# czujnik_smrodu_mkrwan_v02.net
KiCad netlist of a schematic drawn in EAGLE
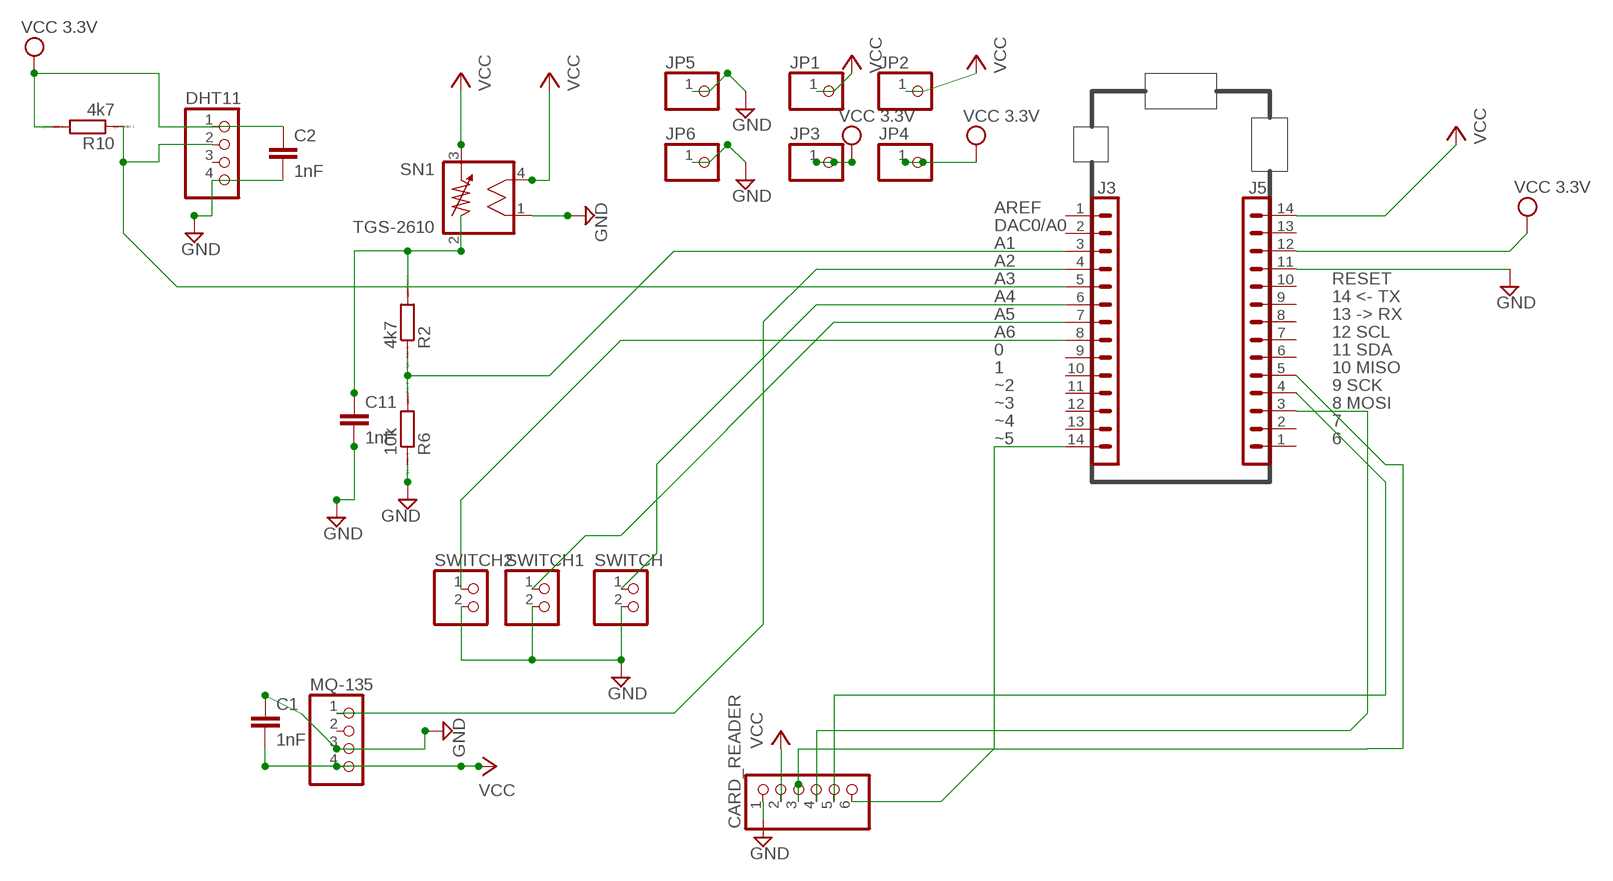
[diagram p0: schematic, sheet 1]

(export (version "E")
  (design (tool "Eeschema 10.0.6"))
  (components
    (comp (ref "C1")
      (value "1nF")
      (footprint "eagle-import:C2.5-3")
      (libsource (lib "eagle-import") (part "C2,5-3"))
    )
    (comp (ref "C2")
      (value "1nF")
      (footprint "eagle-import:C2.5-3")
      (libsource (lib "eagle-import") (part "C2,5-3"))
    )
    (comp (ref "C11")
      (value "1nF")
      (footprint "eagle-import:C2.5-3")
      (libsource (lib "eagle-import") (part "C2,5-3"))
    )
    (comp (ref "CARD_READER")
      (value "PINHD-1X6")
      (footprint "eagle-import:1X06")
      (libsource (lib "eagle-import") (part "PINHD-1X6"))
    )
    (comp (ref "DHT11")
      (value "PINHD-1X4")
      (footprint "eagle-import:1X04")
      (libsource (lib "eagle-import") (part "PINHD-1X4"))
    )
    (comp (ref "J3")
      (value "DNP")
      (footprint "eagle-import:1X14_SMD_TH")
      (fields (field (name "MANUFACTURER") "ELDECO"))
      (libsource (lib "eagle-import") (part "PINHD-1X14-SMTH-SMD"))
    )
    (comp (ref "J5")
      (value "DNP")
      (footprint "eagle-import:1X14_SMD_TH")
      (fields (field (name "MANUFACTURER") "ELDECO"))
      (libsource (lib "eagle-import") (part "PINHD-1X14-SMTH-SMD"))
    )
    (comp (ref "JP1")
      (value "PINHD-1X1")
      (footprint "eagle-import:1X01")
      (libsource (lib "eagle-import") (part "PINHD-1X1"))
    )
    (comp (ref "JP2")
      (value "PINHD-1X1")
      (footprint "eagle-import:1X01")
      (libsource (lib "eagle-import") (part "PINHD-1X1"))
    )
    (comp (ref "JP3")
      (value "PINHD-1X1")
      (footprint "eagle-import:1X01")
      (libsource (lib "eagle-import") (part "PINHD-1X1"))
    )
    (comp (ref "JP4")
      (value "PINHD-1X1")
      (footprint "eagle-import:1X01")
      (libsource (lib "eagle-import") (part "PINHD-1X1"))
    )
    (comp (ref "JP5")
      (value "PINHD-1X1")
      (footprint "eagle-import:1X01")
      (libsource (lib "eagle-import") (part "PINHD-1X1"))
    )
    (comp (ref "JP6")
      (value "PINHD-1X1")
      (footprint "eagle-import:1X01")
      (libsource (lib "eagle-import") (part "PINHD-1X1"))
    )
    (comp (ref "MQ-135")
      (value "PINHD-1X4")
      (footprint "eagle-import:1X04")
      (libsource (lib "eagle-import") (part "PINHD-1X4"))
    )
    (comp (ref "R2")
      (value "4k7")
      (footprint "eagle-import:0207_10")
      (libsource (lib "eagle-import") (part "R0207/10"))
    )
    (comp (ref "R6")
      (value "10k")
      (footprint "eagle-import:0207_10")
      (libsource (lib "eagle-import") (part "R0207/10"))
    )
    (comp (ref "R10")
      (value "4k7")
      (footprint "eagle-import:0207_10")
      (libsource (lib "eagle-import") (part "R0207/10"))
    )
    (comp (ref "SN1")
      (value "TGS-2610")
      (footprint "eagle-import:TGS-2610")
      (libsource (lib "eagle-import") (part "TGS-2610"))
    )
    (comp (ref "SWITCH")
      (value "PINHD-1X2")
      (footprint "eagle-import:1X02")
      (libsource (lib "eagle-import") (part "PINHD-1X2"))
    )
    (comp (ref "SWITCH1")
      (value "PINHD-1X2")
      (footprint "eagle-import:1X02")
      (libsource (lib "eagle-import") (part "PINHD-1X2"))
    )
    (comp (ref "SWITCH2")
      (value "PINHD-1X2")
      (footprint "eagle-import:1X02")
      (libsource (lib "eagle-import") (part "PINHD-1X2"))
    )
  )
  (nets
    (net (code "1") (name "GND") (class "Default")
      (node (ref "C1") (pin "1") (pinfunction "1_1") (pintype "passive"))
      (node (ref "C11") (pin "2") (pinfunction "2_2") (pintype "passive"))
      (node (ref "C2") (pin "2") (pinfunction "2_2") (pintype "passive"))
      (node (ref "CARD_READER") (pin "1") (pinfunction "1_1") (pintype "passive"))
      (node (ref "DHT11") (pin "4") (pinfunction "4_4") (pintype "passive"))
      (node (ref "J5") (pin "11") (pinfunction "11_11") (pintype "passive"))
      (node (ref "JP5") (pin "1") (pinfunction "1_1") (pintype "passive"))
      (node (ref "JP6") (pin "1") (pinfunction "1_1") (pintype "passive"))
      (node (ref "MQ-135") (pin "3") (pinfunction "3_3") (pintype "passive"))
      (node (ref "R6") (pin "1") (pinfunction "1_1") (pintype "passive"))
      (node (ref "SN1") (pin "1") (pinfunction "1_1") (pintype "passive"))
      (node (ref "SWITCH") (pin "2") (pinfunction "2_2") (pintype "passive"))
      (node (ref "SWITCH1") (pin "2") (pinfunction "2_2") (pintype "passive"))
      (node (ref "SWITCH2") (pin "2") (pinfunction "2_2") (pintype "passive"))
    )
    (net (code "2") (name "Net-(C11-Pad1)") (class "Default")
      (node (ref "C11") (pin "1") (pinfunction "1_1") (pintype "passive"))
      (node (ref "R2") (pin "2") (pinfunction "2_2") (pintype "passive"))
      (node (ref "SN1") (pin "2") (pinfunction "2_2") (pintype "passive"))
    )
    (net (code "3") (name "Net-(CARD_READER-Pad3)") (class "Default")
      (node (ref "CARD_READER") (pin "3") (pinfunction "3_3") (pintype "passive"))
      (node (ref "J5") (pin "5") (pinfunction "5_5") (pintype "passive"))
    )
    (net (code "4") (name "Net-(CARD_READER-Pad4)") (class "Default")
      (node (ref "CARD_READER") (pin "4") (pinfunction "4_4") (pintype "passive"))
      (node (ref "J5") (pin "3") (pinfunction "3_3") (pintype "passive"))
    )
    (net (code "5") (name "Net-(CARD_READER-Pad5)") (class "Default")
      (node (ref "CARD_READER") (pin "5") (pinfunction "5_5") (pintype "passive"))
      (node (ref "J5") (pin "4") (pinfunction "4_4") (pintype "passive"))
    )
    (net (code "6") (name "Net-(CARD_READER-Pad6)") (class "Default")
      (node (ref "CARD_READER") (pin "6") (pinfunction "6_6") (pintype "passive"))
      (node (ref "J3") (pin "14") (pinfunction "14_14") (pintype "passive"))
    )
    (net (code "7") (name "Net-(DHT11-Pad2)") (class "Default")
      (node (ref "DHT11") (pin "2") (pinfunction "2_2") (pintype "passive"))
      (node (ref "J3") (pin "5") (pinfunction "5_5") (pintype "passive"))
      (node (ref "R10") (pin "1") (pinfunction "1_1") (pintype "passive"))
    )
    (net (code "8") (name "Net-(J3-Pad3)") (class "Default")
      (node (ref "J3") (pin "3") (pinfunction "3_3") (pintype "passive"))
      (node (ref "R2") (pin "1") (pinfunction "1_1") (pintype "passive"))
      (node (ref "R6") (pin "2") (pinfunction "2_2") (pintype "passive"))
    )
    (net (code "9") (name "Net-(J3-Pad4)") (class "Default")
      (node (ref "J3") (pin "4") (pinfunction "4_4") (pintype "passive"))
      (node (ref "MQ-135") (pin "1") (pinfunction "1_1") (pintype "passive"))
    )
    (net (code "10") (name "Net-(J3-Pad6)") (class "Default")
      (node (ref "J3") (pin "6") (pinfunction "6_6") (pintype "passive"))
      (node (ref "SWITCH") (pin "1") (pinfunction "1_1") (pintype "passive"))
    )
    (net (code "11") (name "Net-(J3-Pad7)") (class "Default")
      (node (ref "J3") (pin "7") (pinfunction "7_7") (pintype "passive"))
      (node (ref "SWITCH1") (pin "1") (pinfunction "1_1") (pintype "passive"))
    )
    (net (code "12") (name "Net-(J3-Pad8)") (class "Default")
      (node (ref "J3") (pin "8") (pinfunction "8_8") (pintype "passive"))
      (node (ref "SWITCH2") (pin "1") (pinfunction "1_1") (pintype "passive"))
    )
    (net (code "13") (name "VCC") (class "Default")
      (node (ref "C1") (pin "2") (pinfunction "2_2") (pintype "passive"))
      (node (ref "C2") (pin "1") (pinfunction "1_1") (pintype "passive"))
      (node (ref "CARD_READER") (pin "2") (pinfunction "2_2") (pintype "passive"))
      (node (ref "DHT11") (pin "1") (pinfunction "1_1") (pintype "passive"))
      (node (ref "J5") (pin "12") (pinfunction "12_12") (pintype "passive"))
      (node (ref "J5") (pin "14") (pinfunction "14_14") (pintype "passive"))
      (node (ref "JP1") (pin "1") (pinfunction "1_1") (pintype "passive"))
      (node (ref "JP2") (pin "1") (pinfunction "1_1") (pintype "passive"))
      (node (ref "JP3") (pin "1") (pinfunction "1_1") (pintype "passive"))
      (node (ref "JP4") (pin "1") (pinfunction "1_1") (pintype "passive"))
      (node (ref "MQ-135") (pin "4") (pinfunction "4_4") (pintype "passive"))
      (node (ref "R10") (pin "2") (pinfunction "2_2") (pintype "passive"))
      (node (ref "SN1") (pin "3") (pinfunction "3_3") (pintype "passive"))
      (node (ref "SN1") (pin "4") (pinfunction "4_4") (pintype "passive"))
    )
    (net (code "14") (name "unconnected-(DHT11-Pad3)") (class "Default")
      (node (ref "DHT11") (pin "3") (pinfunction "3_3") (pintype "passive"))
    )
    (net (code "15") (name "unconnected-(J3-Pad1)") (class "Default")
      (node (ref "J3") (pin "1") (pinfunction "1_1") (pintype "passive"))
    )
    (net (code "16") (name "unconnected-(J3-Pad2)") (class "Default")
      (node (ref "J3") (pin "2") (pinfunction "2_2") (pintype "passive"))
    )
    (net (code "17") (name "unconnected-(J3-Pad9)") (class "Default")
      (node (ref "J3") (pin "9") (pinfunction "9_9") (pintype "passive"))
    )
    (net (code "18") (name "unconnected-(J3-Pad10)") (class "Default")
      (node (ref "J3") (pin "10") (pinfunction "10_10") (pintype "passive"))
    )
    (net (code "19") (name "unconnected-(J3-Pad11)") (class "Default")
      (node (ref "J3") (pin "11") (pinfunction "11_11") (pintype "passive"))
    )
    (net (code "20") (name "unconnected-(J3-Pad12)") (class "Default")
      (node (ref "J3") (pin "12") (pinfunction "12_12") (pintype "passive"))
    )
    (net (code "21") (name "unconnected-(J3-Pad13)") (class "Default")
      (node (ref "J3") (pin "13") (pinfunction "13_13") (pintype "passive"))
    )
    (net (code "22") (name "unconnected-(J5-Pad1)") (class "Default")
      (node (ref "J5") (pin "1") (pinfunction "1_1") (pintype "passive"))
    )
    (net (code "23") (name "unconnected-(J5-Pad2)") (class "Default")
      (node (ref "J5") (pin "2") (pinfunction "2_2") (pintype "passive"))
    )
    (net (code "24") (name "unconnected-(J5-Pad6)") (class "Default")
      (node (ref "J5") (pin "6") (pinfunction "6_6") (pintype "passive"))
    )
    (net (code "25") (name "unconnected-(J5-Pad7)") (class "Default")
      (node (ref "J5") (pin "7") (pinfunction "7_7") (pintype "passive"))
    )
    (net (code "26") (name "unconnected-(J5-Pad8)") (class "Default")
      (node (ref "J5") (pin "8") (pinfunction "8_8") (pintype "passive"))
    )
    (net (code "27") (name "unconnected-(J5-Pad9)") (class "Default")
      (node (ref "J5") (pin "9") (pinfunction "9_9") (pintype "passive"))
    )
    (net (code "28") (name "unconnected-(J5-Pad10)") (class "Default")
      (node (ref "J5") (pin "10") (pinfunction "10_10") (pintype "passive"))
    )
    (net (code "29") (name "unconnected-(J5-Pad13)") (class "Default")
      (node (ref "J5") (pin "13") (pinfunction "13_13") (pintype "passive"))
    )
    (net (code "30") (name "unconnected-(MQ-135-Pad2)") (class "Default")
      (node (ref "MQ-135") (pin "2") (pinfunction "2_2") (pintype "passive"))
    )
  )
)
